# Expansion_Board.net
KiCad netlist of a schematic drawn in Altium Designer
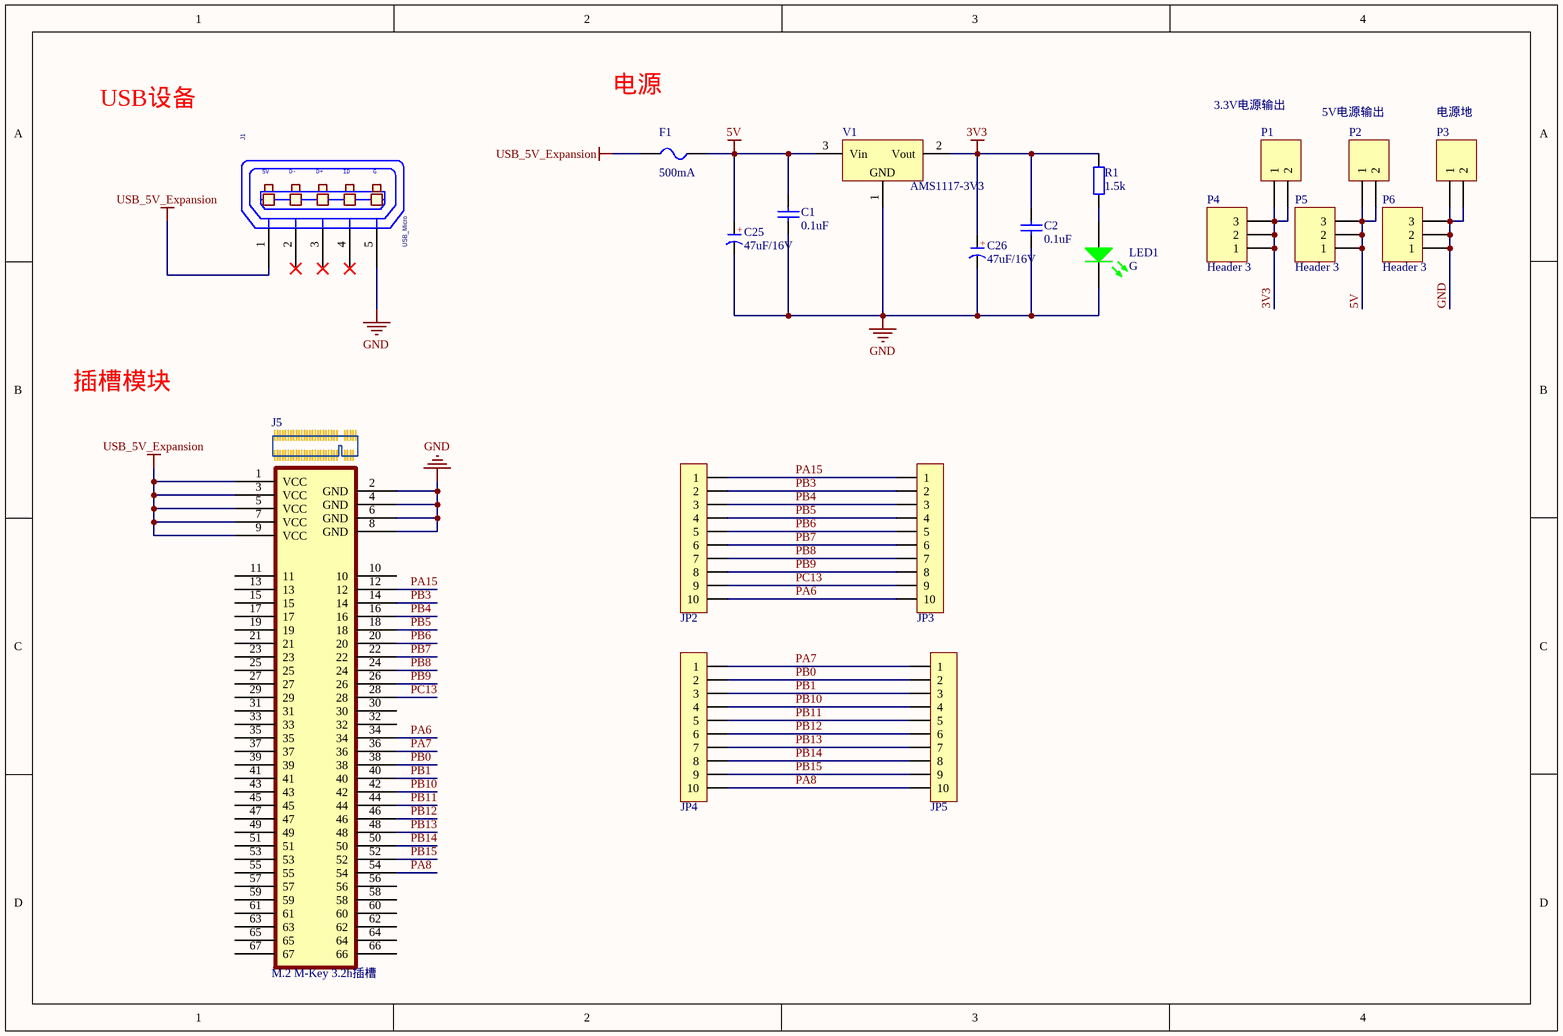
[diagram p0: Expansion_Board.SchDoc]

(export (version "E")
  (design (tool "Eeschema 10.0.6"))
  (components
    (comp (ref "C1")
      (value "0.1uF")
      (footprint "0805_C")
      (description "0805贴片电容")
      (fields (field (name "VOLTAGE") "63V") (field (name "PUBLISHER") "Altium Limited"))
      (libsource (lib "My_Intlib") (part "Cap_SMD"))
    )
    (comp (ref "C2")
      (value "0.1uF")
      (footprint "0805_C")
      (description "0805贴片电容")
      (fields (field (name "VOLTAGE") "63V") (field (name "PUBLISHER") "Altium Limited"))
      (libsource (lib "My_Intlib") (part "Cap_SMD"))
    )
    (comp (ref "C25")
      (value "47uF/16V")
      (footprint "CM C(5*5.4)")
      (description "电解电容")
      (libsource (lib "My_Intlib") (part "Cap_ELE"))
    )
    (comp (ref "C26")
      (value "47uF/16V")
      (footprint "CM C(5*5.4)")
      (description "电解电容")
      (libsource (lib "My_Intlib") (part "Cap_ELE"))
    )
    (comp (ref "F1")
      (value "500mA")
      (footprint "FU 1210")
      (description "贴片保险丝")
      (fields (field (name "版权归属") "源创客"))
      (libsource (lib "My_Intlib") (part "FU"))
    )
    (comp (ref "J1")
      (value "USB_Micro")
      (footprint "USB-MICRO")
      (libsource (lib "My_Intlib") (part "USB_Micro"))
    )
    (comp (ref "J5")
      (value "M.2 M-Key 3.2h插槽")
      (footprint "M-Key Socket")
      (libsource (lib "My_Intlib") (part "M-Key Socket"))
    )
    (comp (ref "JP2")
      (value "HDR-1X10")
      (footprint "HDR2.54-LI-10P")
      (description "10P接插件")
      (fields (field (name "版权归属") "源创客"))
      (libsource (lib "") (part "Header 10_1"))
    )
    (comp (ref "JP3")
      (value "HDR-1X10")
      (footprint "HDR2.54-M-LI-10P")
      (description "10P接插件")
      (fields (field (name "版权归属") "源创客"))
      (libsource (lib "My_Intlib") (part "Header 10"))
    )
    (comp (ref "JP4")
      (value "HDR-1X10")
      (footprint "HDR2.54-LI-10P")
      (description "10P接插件")
      (fields (field (name "版权归属") "源创客"))
      (libsource (lib "") (part "Header 10_1"))
    )
    (comp (ref "JP5")
      (value "HDR-1X10")
      (footprint "HDR2.54-M-LI-10P")
      (description "10P接插件")
      (fields (field (name "版权归属") "源创客"))
      (libsource (lib "My_Intlib") (part "Header 10"))
    )
    (comp (ref "LED1")
      (value "G")
      (footprint "LED 0805G")
      (description "绿色LED")
      (fields (field (name "PUBLISHER") "Altium Limited"))
      (libsource (lib "My_Intlib") (part "LED_G"))
    )
    (comp (ref "P1")
      (value "3.3V电源输出")
      (footprint "KF128-5.08-2P")
      (description "2P接插件")
      (fields (field (name "PUBLISHER") "Altium Limited"))
      (libsource (lib "My_Intlib") (part "Header 2"))
    )
    (comp (ref "P2")
      (value "5V电源输出")
      (footprint "KF128-5.08-2P")
      (description "2P接插件")
      (fields (field (name "PUBLISHER") "Altium Limited"))
      (libsource (lib "My_Intlib") (part "Header 2"))
    )
    (comp (ref "P3")
      (value "电源地")
      (footprint "KF128-5.08-2P")
      (description "2P接插件")
      (fields (field (name "PUBLISHER") "Altium Limited"))
      (libsource (lib "My_Intlib") (part "Header 2"))
    )
    (comp (ref "P4")
      (value "Header 3")
      (footprint "HDR-1X3_M")
      (description "3P接插件")
      (fields (field (name "PUBLISHER") "Altium Limited"))
      (libsource (lib "My_Intlib") (part "Header 3"))
    )
    (comp (ref "P5")
      (value "Header 3")
      (footprint "HDR-1X3_M")
      (description "3P接插件")
      (fields (field (name "PUBLISHER") "Altium Limited"))
      (libsource (lib "My_Intlib") (part "Header 3"))
    )
    (comp (ref "P6")
      (value "Header 3")
      (footprint "HDR-1X3_M")
      (description "3P接插件")
      (fields (field (name "PUBLISHER") "Altium Limited"))
      (libsource (lib "My_Intlib") (part "Header 3"))
    )
    (comp (ref "R1")
      (value "1.5k")
      (footprint "0805_R")
      (description "0805贴片电阻")
      (fields (field (name "PUBLISHER") "Altium Limited"))
      (libsource (lib "My_Intlib") (part "Res_SMD"))
    )
    (comp (ref "V1")
      (value "AMS1117-3V3")
      (footprint "SOT223")
      (description "三端稳压芯片")
      (fields (field (name "版权归属") "源创客"))
      (libsource (lib "My_Intlib") (part "AMS1117"))
    )
  )
  (nets
    (net (code "1") (name "/PA6") (class "Default")
      (node (ref "J5") (pin "34") (pinfunction "34_34") (pintype "passive"))
      (node (ref "JP2") (pin "10") (pinfunction "10_10") (pintype "passive"))
      (node (ref "JP3") (pin "10") (pinfunction "10_10") (pintype "passive"))
    )
    (net (code "2") (name "/PA7") (class "Default")
      (node (ref "J5") (pin "36") (pinfunction "36_36") (pintype "passive"))
      (node (ref "JP4") (pin "1") (pinfunction "1_1") (pintype "passive"))
      (node (ref "JP5") (pin "1") (pinfunction "1_1") (pintype "passive"))
    )
    (net (code "3") (name "/PA8") (class "Default")
      (node (ref "J5") (pin "54") (pinfunction "54_54") (pintype "passive"))
      (node (ref "JP4") (pin "10") (pinfunction "10_10") (pintype "passive"))
      (node (ref "JP5") (pin "10") (pinfunction "10_10") (pintype "passive"))
    )
    (net (code "4") (name "/PA15") (class "Default")
      (node (ref "J5") (pin "12") (pinfunction "12_12") (pintype "passive"))
      (node (ref "JP2") (pin "1") (pinfunction "1_1") (pintype "passive"))
      (node (ref "JP3") (pin "1") (pinfunction "1_1") (pintype "passive"))
    )
    (net (code "5") (name "/PB0") (class "Default")
      (node (ref "J5") (pin "38") (pinfunction "38_38") (pintype "passive"))
      (node (ref "JP4") (pin "2") (pinfunction "2_2") (pintype "passive"))
      (node (ref "JP5") (pin "2") (pinfunction "2_2") (pintype "passive"))
    )
    (net (code "6") (name "/PB1") (class "Default")
      (node (ref "J5") (pin "40") (pinfunction "40_40") (pintype "passive"))
      (node (ref "JP4") (pin "3") (pinfunction "3_3") (pintype "passive"))
      (node (ref "JP5") (pin "3") (pinfunction "3_3") (pintype "passive"))
    )
    (net (code "7") (name "/PB3") (class "Default")
      (node (ref "J5") (pin "14") (pinfunction "14_14") (pintype "passive"))
      (node (ref "JP2") (pin "2") (pinfunction "2_2") (pintype "passive"))
      (node (ref "JP3") (pin "2") (pinfunction "2_2") (pintype "passive"))
    )
    (net (code "8") (name "/PB4") (class "Default")
      (node (ref "J5") (pin "16") (pinfunction "16_16") (pintype "passive"))
      (node (ref "JP2") (pin "3") (pinfunction "3_3") (pintype "passive"))
      (node (ref "JP3") (pin "3") (pinfunction "3_3") (pintype "passive"))
    )
    (net (code "9") (name "/PB5") (class "Default")
      (node (ref "J5") (pin "18") (pinfunction "18_18") (pintype "passive"))
      (node (ref "JP2") (pin "4") (pinfunction "4_4") (pintype "passive"))
      (node (ref "JP3") (pin "4") (pinfunction "4_4") (pintype "passive"))
    )
    (net (code "10") (name "/PB6") (class "Default")
      (node (ref "J5") (pin "20") (pinfunction "20_20") (pintype "passive"))
      (node (ref "JP2") (pin "5") (pinfunction "5_5") (pintype "passive"))
      (node (ref "JP3") (pin "5") (pinfunction "5_5") (pintype "passive"))
    )
    (net (code "11") (name "/PB7") (class "Default")
      (node (ref "J5") (pin "22") (pinfunction "22_22") (pintype "passive"))
      (node (ref "JP2") (pin "6") (pinfunction "6_6") (pintype "passive"))
      (node (ref "JP3") (pin "6") (pinfunction "6_6") (pintype "passive"))
    )
    (net (code "12") (name "/PB8") (class "Default")
      (node (ref "J5") (pin "24") (pinfunction "24_24") (pintype "passive"))
      (node (ref "JP2") (pin "7") (pinfunction "7_7") (pintype "passive"))
      (node (ref "JP3") (pin "7") (pinfunction "7_7") (pintype "passive"))
    )
    (net (code "13") (name "/PB9") (class "Default")
      (node (ref "J5") (pin "26") (pinfunction "26_26") (pintype "passive"))
      (node (ref "JP2") (pin "8") (pinfunction "8_8") (pintype "passive"))
      (node (ref "JP3") (pin "8") (pinfunction "8_8") (pintype "passive"))
    )
    (net (code "14") (name "/PB10") (class "Default")
      (node (ref "J5") (pin "42") (pinfunction "42_42") (pintype "passive"))
      (node (ref "JP4") (pin "4") (pinfunction "4_4") (pintype "passive"))
      (node (ref "JP5") (pin "4") (pinfunction "4_4") (pintype "passive"))
    )
    (net (code "15") (name "/PB11") (class "Default")
      (node (ref "J5") (pin "44") (pinfunction "44_44") (pintype "passive"))
      (node (ref "JP4") (pin "5") (pinfunction "5_5") (pintype "passive"))
      (node (ref "JP5") (pin "5") (pinfunction "5_5") (pintype "passive"))
    )
    (net (code "16") (name "/PB12") (class "Default")
      (node (ref "J5") (pin "46") (pinfunction "46_46") (pintype "passive"))
      (node (ref "JP4") (pin "6") (pinfunction "6_6") (pintype "passive"))
      (node (ref "JP5") (pin "6") (pinfunction "6_6") (pintype "passive"))
    )
    (net (code "17") (name "/PB13") (class "Default")
      (node (ref "J5") (pin "48") (pinfunction "48_48") (pintype "passive"))
      (node (ref "JP4") (pin "7") (pinfunction "7_7") (pintype "passive"))
      (node (ref "JP5") (pin "7") (pinfunction "7_7") (pintype "passive"))
    )
    (net (code "18") (name "/PB14") (class "Default")
      (node (ref "J5") (pin "50") (pinfunction "50_50") (pintype "passive"))
      (node (ref "JP4") (pin "8") (pinfunction "8_8") (pintype "passive"))
      (node (ref "JP5") (pin "8") (pinfunction "8_8") (pintype "passive"))
    )
    (net (code "19") (name "/PB15") (class "Default")
      (node (ref "J5") (pin "52") (pinfunction "52_52") (pintype "passive"))
      (node (ref "JP4") (pin "9") (pinfunction "9_9") (pintype "passive"))
      (node (ref "JP5") (pin "9") (pinfunction "9_9") (pintype "passive"))
    )
    (net (code "20") (name "/PC13") (class "Default")
      (node (ref "J5") (pin "28") (pinfunction "28_28") (pintype "passive"))
      (node (ref "JP2") (pin "9") (pinfunction "9_9") (pintype "passive"))
      (node (ref "JP3") (pin "9") (pinfunction "9_9") (pintype "passive"))
    )
    (net (code "21") (name "3V3") (class "Default")
      (node (ref "C2") (pin "2") (pinfunction "2_2") (pintype "passive"))
      (node (ref "C26") (pin "1") (pinfunction "A_1") (pintype "passive"))
      (node (ref "P1") (pin "1") (pinfunction "1_1") (pintype "passive"))
      (node (ref "P1") (pin "2") (pinfunction "2_2") (pintype "passive"))
      (node (ref "P4") (pin "1") (pinfunction "1_1") (pintype "passive"))
      (node (ref "P4") (pin "2") (pinfunction "2_2") (pintype "passive"))
      (node (ref "P4") (pin "3") (pinfunction "3_3") (pintype "passive"))
      (node (ref "R1") (pin "2") (pinfunction "2_2") (pintype "passive"))
      (node (ref "V1") (pin "2") (pinfunction "Vout_2") (pintype "passive"))
    )
    (net (code "22") (name "5V") (class "Default")
      (node (ref "C1") (pin "2") (pinfunction "2_2") (pintype "passive"))
      (node (ref "C25") (pin "1") (pinfunction "A_1") (pintype "passive"))
      (node (ref "F1") (pin "2") (pinfunction "2_2") (pintype "passive"))
      (node (ref "P2") (pin "1") (pinfunction "1_1") (pintype "passive"))
      (node (ref "P2") (pin "2") (pinfunction "2_2") (pintype "passive"))
      (node (ref "P5") (pin "1") (pinfunction "1_1") (pintype "passive"))
      (node (ref "P5") (pin "2") (pinfunction "2_2") (pintype "passive"))
      (node (ref "P5") (pin "3") (pinfunction "3_3") (pintype "passive"))
      (node (ref "V1") (pin "3") (pinfunction "Vin_3") (pintype "passive"))
    )
    (net (code "23") (name "GND") (class "Default")
      (node (ref "C1") (pin "1") (pinfunction "1_1") (pintype "passive"))
      (node (ref "C2") (pin "1") (pinfunction "1_1") (pintype "passive"))
      (node (ref "C25") (pin "2") (pinfunction "K_2") (pintype "passive"))
      (node (ref "C26") (pin "2") (pinfunction "K_2") (pintype "passive"))
      (node (ref "J1") (pin "5") (pinfunction "P5_5") (pintype "passive"))
      (node (ref "J5") (pin "2") (pinfunction "GND_2") (pintype "passive"))
      (node (ref "J5") (pin "4") (pinfunction "GND_4") (pintype "passive"))
      (node (ref "J5") (pin "6") (pinfunction "GND_6") (pintype "passive"))
      (node (ref "J5") (pin "8") (pinfunction "GND_8") (pintype "passive"))
      (node (ref "LED1") (pin "2") (pinfunction "K_2") (pintype "passive"))
      (node (ref "P3") (pin "1") (pinfunction "1_1") (pintype "passive"))
      (node (ref "P3") (pin "2") (pinfunction "2_2") (pintype "passive"))
      (node (ref "P6") (pin "1") (pinfunction "1_1") (pintype "passive"))
      (node (ref "P6") (pin "2") (pinfunction "2_2") (pintype "passive"))
      (node (ref "P6") (pin "3") (pinfunction "3_3") (pintype "passive"))
      (node (ref "V1") (pin "1") (pinfunction "GND_1") (pintype "passive"))
    )
    (net (code "24") (name "Net-(LED1-A)") (class "Default")
      (node (ref "LED1") (pin "1") (pinfunction "A_1") (pintype "passive"))
      (node (ref "R1") (pin "1") (pinfunction "1_1") (pintype "passive"))
    )
    (net (code "25") (name "USB_5V_Expansion") (class "Default")
      (node (ref "F1") (pin "1") (pinfunction "1_1") (pintype "passive"))
      (node (ref "J1") (pin "1") (pinfunction "P1_1") (pintype "passive"))
      (node (ref "J5") (pin "1") (pinfunction "VCC_1") (pintype "passive"))
      (node (ref "J5") (pin "3") (pinfunction "VCC_3") (pintype "passive"))
      (node (ref "J5") (pin "5") (pinfunction "VCC_5") (pintype "passive"))
      (node (ref "J5") (pin "7") (pinfunction "VCC_7") (pintype "passive"))
      (node (ref "J5") (pin "9") (pinfunction "VCC_9") (pintype "passive"))
    )
    (net (code "26") (name "unconnected-(J1-P2-Pad2)") (class "Default")
      (node (ref "J1") (pin "2") (pinfunction "P2_2") (pintype "passive+no_connect"))
    )
    (net (code "27") (name "unconnected-(J1-P3-Pad3)") (class "Default")
      (node (ref "J1") (pin "3") (pinfunction "P3_3") (pintype "passive+no_connect"))
    )
    (net (code "28") (name "unconnected-(J1-P4-Pad4)") (class "Default")
      (node (ref "J1") (pin "4") (pinfunction "P4_4") (pintype "passive+no_connect"))
    )
    (net (code "29") (name "unconnected-(J5-Pad10)") (class "Default")
      (node (ref "J5") (pin "10") (pinfunction "10_10") (pintype "passive"))
    )
    (net (code "30") (name "unconnected-(J5-Pad11)") (class "Default")
      (node (ref "J5") (pin "11") (pinfunction "11_11") (pintype "passive"))
    )
    (net (code "31") (name "unconnected-(J5-Pad13)") (class "Default")
      (node (ref "J5") (pin "13") (pinfunction "13_13") (pintype "passive"))
    )
    (net (code "32") (name "unconnected-(J5-Pad15)") (class "Default")
      (node (ref "J5") (pin "15") (pinfunction "15_15") (pintype "passive"))
    )
    (net (code "33") (name "unconnected-(J5-Pad17)") (class "Default")
      (node (ref "J5") (pin "17") (pinfunction "17_17") (pintype "passive"))
    )
    (net (code "34") (name "unconnected-(J5-Pad19)") (class "Default")
      (node (ref "J5") (pin "19") (pinfunction "19_19") (pintype "passive"))
    )
    (net (code "35") (name "unconnected-(J5-Pad21)") (class "Default")
      (node (ref "J5") (pin "21") (pinfunction "21_21") (pintype "passive"))
    )
    (net (code "36") (name "unconnected-(J5-Pad23)") (class "Default")
      (node (ref "J5") (pin "23") (pinfunction "23_23") (pintype "passive"))
    )
    (net (code "37") (name "unconnected-(J5-Pad25)") (class "Default")
      (node (ref "J5") (pin "25") (pinfunction "25_25") (pintype "passive"))
    )
    (net (code "38") (name "unconnected-(J5-Pad27)") (class "Default")
      (node (ref "J5") (pin "27") (pinfunction "27_27") (pintype "passive"))
    )
    (net (code "39") (name "unconnected-(J5-Pad29)") (class "Default")
      (node (ref "J5") (pin "29") (pinfunction "29_29") (pintype "passive"))
    )
    (net (code "40") (name "unconnected-(J5-Pad30)") (class "Default")
      (node (ref "J5") (pin "30") (pinfunction "30_30") (pintype "passive"))
    )
    (net (code "41") (name "unconnected-(J5-Pad31)") (class "Default")
      (node (ref "J5") (pin "31") (pinfunction "31_31") (pintype "passive"))
    )
    (net (code "42") (name "unconnected-(J5-Pad32)") (class "Default")
      (node (ref "J5") (pin "32") (pinfunction "32_32") (pintype "passive"))
    )
    (net (code "43") (name "unconnected-(J5-Pad33)") (class "Default")
      (node (ref "J5") (pin "33") (pinfunction "33_33") (pintype "passive"))
    )
    (net (code "44") (name "unconnected-(J5-Pad35)") (class "Default")
      (node (ref "J5") (pin "35") (pinfunction "35_35") (pintype "passive"))
    )
    (net (code "45") (name "unconnected-(J5-Pad37)") (class "Default")
      (node (ref "J5") (pin "37") (pinfunction "37_37") (pintype "passive"))
    )
    (net (code "46") (name "unconnected-(J5-Pad39)") (class "Default")
      (node (ref "J5") (pin "39") (pinfunction "39_39") (pintype "passive"))
    )
    (net (code "47") (name "unconnected-(J5-Pad41)") (class "Default")
      (node (ref "J5") (pin "41") (pinfunction "41_41") (pintype "passive"))
    )
    (net (code "48") (name "unconnected-(J5-Pad43)") (class "Default")
      (node (ref "J5") (pin "43") (pinfunction "43_43") (pintype "passive"))
    )
    (net (code "49") (name "unconnected-(J5-Pad45)") (class "Default")
      (node (ref "J5") (pin "45") (pinfunction "45_45") (pintype "passive"))
    )
    (net (code "50") (name "unconnected-(J5-Pad47)") (class "Default")
      (node (ref "J5") (pin "47") (pinfunction "47_47") (pintype "passive"))
    )
    (net (code "51") (name "unconnected-(J5-Pad49)") (class "Default")
      (node (ref "J5") (pin "49") (pinfunction "49_49") (pintype "passive"))
    )
    (net (code "52") (name "unconnected-(J5-Pad51)") (class "Default")
      (node (ref "J5") (pin "51") (pinfunction "51_51") (pintype "passive"))
    )
    (net (code "53") (name "unconnected-(J5-Pad53)") (class "Default")
      (node (ref "J5") (pin "53") (pinfunction "53_53") (pintype "passive"))
    )
    (net (code "54") (name "unconnected-(J5-Pad55)") (class "Default")
      (node (ref "J5") (pin "55") (pinfunction "55_55") (pintype "passive"))
    )
    (net (code "55") (name "unconnected-(J5-Pad56)") (class "Default")
      (node (ref "J5") (pin "56") (pinfunction "56_56") (pintype "passive"))
    )
    (net (code "56") (name "unconnected-(J5-Pad57)") (class "Default")
      (node (ref "J5") (pin "57") (pinfunction "57_57") (pintype "passive"))
    )
    (net (code "57") (name "unconnected-(J5-Pad58)") (class "Default")
      (node (ref "J5") (pin "58") (pinfunction "58_58") (pintype "passive"))
    )
    (net (code "58") (name "unconnected-(J5-Pad59)") (class "Default")
      (node (ref "J5") (pin "59") (pinfunction "59_59") (pintype "passive"))
    )
    (net (code "59") (name "unconnected-(J5-Pad60)") (class "Default")
      (node (ref "J5") (pin "60") (pinfunction "60_60") (pintype "passive"))
    )
    (net (code "60") (name "unconnected-(J5-Pad61)") (class "Default")
      (node (ref "J5") (pin "61") (pinfunction "61_61") (pintype "passive"))
    )
    (net (code "61") (name "unconnected-(J5-Pad62)") (class "Default")
      (node (ref "J5") (pin "62") (pinfunction "62_62") (pintype "passive"))
    )
    (net (code "62") (name "unconnected-(J5-Pad63)") (class "Default")
      (node (ref "J5") (pin "63") (pinfunction "63_63") (pintype "passive"))
    )
    (net (code "63") (name "unconnected-(J5-Pad64)") (class "Default")
      (node (ref "J5") (pin "64") (pinfunction "64_64") (pintype "passive"))
    )
    (net (code "64") (name "unconnected-(J5-Pad65)") (class "Default")
      (node (ref "J5") (pin "65") (pinfunction "65_65") (pintype "passive"))
    )
    (net (code "65") (name "unconnected-(J5-Pad66)") (class "Default")
      (node (ref "J5") (pin "66") (pinfunction "66_66") (pintype "passive"))
    )
    (net (code "66") (name "unconnected-(J5-Pad67)") (class "Default")
      (node (ref "J5") (pin "67") (pinfunction "67_67") (pintype "passive"))
    )
  )
)
